# PG05_Power_Conversions.net
KiCad netlist of a schematic drawn in Altium Designer
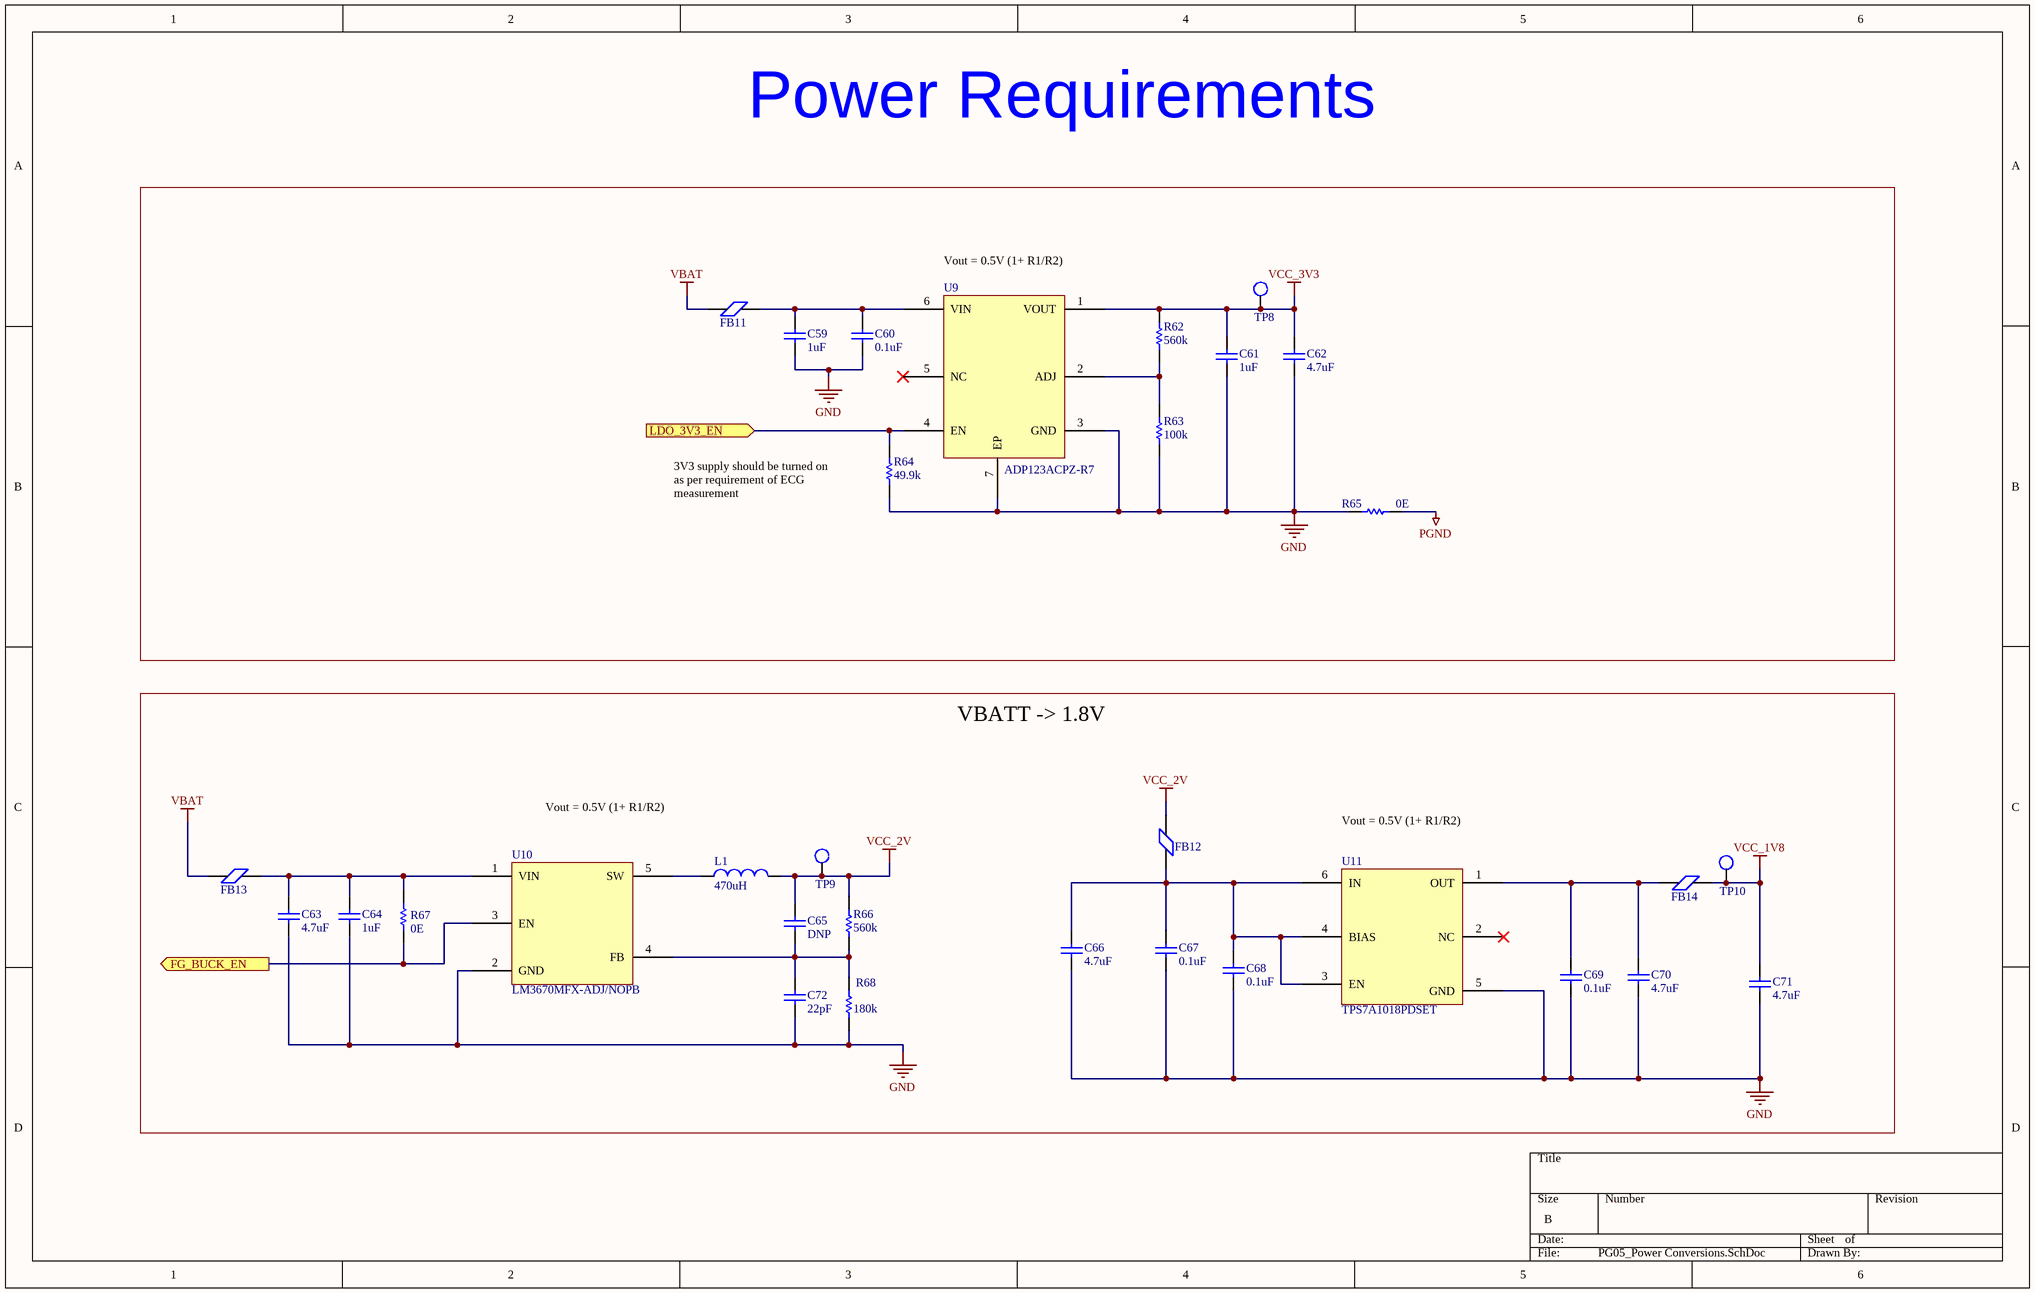
[diagram p0: PG05_Power Conversions.SchDoc]

(export (version "E")
  (design (tool "Eeschema 10.0.6"))
  (components
    (comp (ref "C59")
      (value "1uF")
      (footprint "0805C")
      (description "CAP CER 1UF 25V X7R 0805")
      (libsource (lib "Smart Ring Components") (part "CAP_0805_1uF_25V"))
    )
    (comp (ref "C60")
      (value "0.1uF")
      (footprint "0402C")
      (description "CAP CER 0.1UF 50V X7R 0402")
      (libsource (lib "Smart Ring Components") (part "CAP_0402_0.1uF_50V"))
    )
    (comp (ref "C61")
      (value "1uF")
      (footprint "0805C")
      (description "CAP CER 1UF 25V X7R 0805")
      (libsource (lib "Smart Ring Components") (part "CAP_0805_1uF_25V"))
    )
    (comp (ref "C62")
      (value "4.7uF")
      (footprint "0805C")
      (description "CAP CER MLCC 4.7uF X7R 16V  0805")
      (libsource (lib "Smart Ring Components") (part "CAP_0805_4.7uF_16V"))
    )
    (comp (ref "C63")
      (value "4.7uF")
      (footprint "0805C")
      (description "CAP CER MLCC 4.7uF X7R 16V  0805")
      (libsource (lib "Smart Ring Components") (part "CAP_0805_4.7uF_16V"))
    )
    (comp (ref "C64")
      (value "1uF")
      (footprint "0805C")
      (description "CAP CER 1UF 25V X7R 0805")
      (libsource (lib "Smart Ring Components") (part "CAP_0805_1uF_25V"))
    )
    (comp (ref "C65")
      (value "DNP")
      (footprint "0402C")
      (description "CAP CER DNP 0402")
      (fields (field (name "MFR") "Generic"))
      (libsource (lib "Smart Ring Components") (part "CAP_0402_DNP"))
    )
    (comp (ref "C66")
      (value "4.7uF")
      (footprint "0805C")
      (description "CAP CER MLCC 4.7uF X7R 16V  0805")
      (libsource (lib "Smart Ring Components") (part "CAP_0805_4.7uF_16V"))
    )
    (comp (ref "C67")
      (value "0.1uF")
      (footprint "0402C")
      (description "CAP CER 0.1UF 50V X7R 0402")
      (libsource (lib "Smart Ring Components") (part "CAP_0402_0.1uF_50V"))
    )
    (comp (ref "C68")
      (value "0.1uF")
      (footprint "0402C")
      (description "CAP CER 0.1UF 50V X7R 0402")
      (libsource (lib "Smart Ring Components") (part "CAP_0402_0.1uF_50V"))
    )
    (comp (ref "C69")
      (value "0.1uF")
      (footprint "0402C")
      (description "CAP CER 0.1UF 50V X7R 0402")
      (libsource (lib "Smart Ring Components") (part "CAP_0402_0.1uF_50V"))
    )
    (comp (ref "C70")
      (value "4.7uF")
      (footprint "0805C")
      (description "CAP CER MLCC 4.7uF X7R 16V  0805")
      (libsource (lib "Smart Ring Components") (part "CAP_0805_4.7uF_16V"))
    )
    (comp (ref "C71")
      (value "4.7uF")
      (footprint "0805C")
      (description "CAP CER MLCC 4.7uF X7R 16V  0805")
      (libsource (lib "Smart Ring Components") (part "CAP_0805_4.7uF_16V"))
    )
    (comp (ref "C72")
      (value "22pF")
      (footprint "0402C")
      (description "CAP CER 22PF 50V C0G 0402")
      (fields (field (name "MFR") "Generic"))
      (libsource (lib "Smart Ring Components") (part "CAP_0402_22pF"))
    )
    (comp (ref "FB11")
      (value "Ferrite Bead")
      (footprint "0402R")
      (description "CHIP BEAD 600 OHM 0402 300mA")
      (fields (field (name "MFR") "Walsin") (field (name "MPN") "WLBD1005K2U601TP"))
      (libsource (lib "Smart Ring Components") (part "Ferrite Bead"))
    )
    (comp (ref "FB12")
      (value "Ferrite Bead")
      (footprint "0402R")
      (description "CHIP BEAD 600 OHM 0402 300mA")
      (fields (field (name "MFR") "Walsin") (field (name "MPN") "WLBD1005K2U601TP"))
      (libsource (lib "Smart Ring Components") (part "Ferrite Bead"))
    )
    (comp (ref "FB13")
      (value "Ferrite Bead")
      (footprint "0402R")
      (description "CHIP BEAD 600 OHM 0402 300mA")
      (fields (field (name "MFR") "Walsin") (field (name "MPN") "WLBD1005K2U601TP"))
      (libsource (lib "Smart Ring Components") (part "Ferrite Bead"))
    )
    (comp (ref "FB14")
      (value "Ferrite Bead")
      (footprint "0402R")
      (description "CHIP BEAD 600 OHM 0402 300mA")
      (fields (field (name "MFR") "Walsin") (field (name "MPN") "WLBD1005K2U601TP"))
      (libsource (lib "Smart Ring Components") (part "Ferrite Bead"))
    )
    (comp (ref "L1")
      (value "470uH")
      (footprint "NR6028T3R0N")
      (description "FIXED IND 470UH 105MA 14.3OHM SM")
      (fields (field (name "MFR") "Bourns") (field (name "MPN") "SDR0302-471KL"))
      (libsource (lib "Smart Ring Components") (part "IND_470uH"))
    )
    (comp (ref "R62")
      (value "560k")
      (footprint "0402R")
      (description "RES 560K OHM 1% 1/16W 0402")
      (fields (field (name "MFR") "Generic"))
      (libsource (lib "Smart Ring Components") (part "RES_0402_560k"))
    )
    (comp (ref "R63")
      (value "100k")
      (footprint "0402R")
      (description "RES 100K OHM 1% 1/16W 0402")
      (fields (field (name "MFR") "Generic"))
      (libsource (lib "Smart Ring Components") (part "RES_0402_100k"))
    )
    (comp (ref "R64")
      (value "49.9k")
      (footprint "0402R")
      (description "RES 49.9K OHM 1% 1/16W 0402")
      (fields (field (name "MFR") "Generic"))
      (libsource (lib "Smart Ring Components") (part "RES_0402_49.9k"))
    )
    (comp (ref "R65")
      (value "0E")
      (footprint "0402R")
      (description "RES 0 OHM JUMPER 1/16W 0402")
      (fields (field (name "MFR") "Generic"))
      (libsource (lib "Smart Ring Components") (part "RES_0402_0E"))
    )
    (comp (ref "R66")
      (value "560k")
      (footprint "0402R")
      (description "RES 560K OHM 1% 1/16W 0402")
      (fields (field (name "MFR") "Generic"))
      (libsource (lib "Smart Ring Components") (part "RES_0402_560k"))
    )
    (comp (ref "R67")
      (value "0E")
      (footprint "0402R")
      (description "RES 0 OHM JUMPER 1/16W 0402")
      (fields (field (name "MFR") "Generic"))
      (libsource (lib "Smart Ring Components") (part "RES_0402_0E"))
    )
    (comp (ref "R68")
      (value "180k")
      (footprint "0402R")
      (description "RES 180K OHM 1% 1/16W 0402")
      (fields (field (name "MFR") "Generic"))
      (libsource (lib "Smart Ring Components") (part "RES_0402_180k"))
    )
    (comp (ref "TP8")
      (value "Test_Point")
      (footprint "TP")
      (libsource (lib "Smart Ring Components") (part "Test_Point"))
    )
    (comp (ref "TP9")
      (value "Test_Point")
      (footprint "TP")
      (libsource (lib "Smart Ring Components") (part "Test_Point"))
    )
    (comp (ref "TP10")
      (value "Test_Point")
      (footprint "TP")
      (libsource (lib "Smart Ring Components") (part "Test_Point"))
    )
    (comp (ref "U9")
      (value "ADP123ACPZ-R7")
      (footprint "ADP123ACPZ-R7")
      (description "IC REG LIN POS ADJ 300MA 6LFCSP")
      (fields (field (name "MFR") "Analog Devices"))
      (libsource (lib "Smart Ring Components") (part "LDO_ADP123ACPZ-R7"))
    )
    (comp (ref "U10")
      (value "LM3670MFX-ADJ/NOPB")
      (footprint "LM3670MFX-ADJ/NOPB")
      (description "IC REG BUCK ADJ 350MA SOT23-5")
      (fields (field (name "MFR") "Texas Instruments"))
      (libsource (lib "Smart Ring Components") (part "Buck_LM3670MFX-ADJ/NOPB"))
    )
    (comp (ref "U11")
      (value "TPS7A1018PDSET")
      (footprint "TPS7A1018PDSET")
      (description "IC REG LINEAR 1.8V 300MA 6WSON")
      (fields (field (name "MFR") "TI"))
      (libsource (lib "Smart Ring Components") (part "LDO_TPS7A1018PDSET"))
    )
  )
  (nets
    (net (code "1") (name "/FG_BUCK_EN") (class "Default")
      (node (ref "R67") (pin "1") (pinfunction "1_1") (pintype "passive"))
      (node (ref "U10") (pin "3") (pinfunction "EN_3") (pintype "passive"))
    )
    (net (code "2") (name "/LDO_3V3_EN") (class "Default")
      (node (ref "R64") (pin "2") (pinfunction "2_2") (pintype "passive"))
      (node (ref "U9") (pin "4") (pinfunction "EN_4") (pintype "power_in"))
    )
    (net (code "3") (name "GND") (class "Default")
      (node (ref "C59") (pin "1") (pinfunction "1_1") (pintype "passive"))
      (node (ref "C60") (pin "1") (pinfunction "1_1") (pintype "passive"))
      (node (ref "C61") (pin "1") (pinfunction "1_1") (pintype "passive"))
      (node (ref "C62") (pin "1") (pinfunction "1_1") (pintype "passive"))
      (node (ref "C63") (pin "1") (pinfunction "1_1") (pintype "passive"))
      (node (ref "C64") (pin "1") (pinfunction "1_1") (pintype "passive"))
      (node (ref "C66") (pin "1") (pinfunction "1_1") (pintype "passive"))
      (node (ref "C67") (pin "1") (pinfunction "1_1") (pintype "passive"))
      (node (ref "C68") (pin "1") (pinfunction "1_1") (pintype "passive"))
      (node (ref "C69") (pin "1") (pinfunction "1_1") (pintype "passive"))
      (node (ref "C70") (pin "1") (pinfunction "1_1") (pintype "passive"))
      (node (ref "C71") (pin "1") (pinfunction "1_1") (pintype "passive"))
      (node (ref "C72") (pin "1") (pinfunction "1_1") (pintype "passive"))
      (node (ref "R63") (pin "1") (pinfunction "1_1") (pintype "passive"))
      (node (ref "R64") (pin "1") (pinfunction "1_1") (pintype "passive"))
      (node (ref "R65") (pin "1") (pinfunction "1_1") (pintype "passive"))
      (node (ref "R68") (pin "1") (pinfunction "1_1") (pintype "passive"))
      (node (ref "U10") (pin "2") (pinfunction "GND_2") (pintype "power_in"))
      (node (ref "U11") (pin "5") (pinfunction "GND_5") (pintype "power_in"))
      (node (ref "U9") (pin "3") (pinfunction "GND_3") (pintype "power_in"))
      (node (ref "U9") (pin "7") (pinfunction "EP_7") (pintype "power_in"))
    )
    (net (code "4") (name "Net-(U9-ADJ)") (class "Default")
      (node (ref "R62") (pin "1") (pinfunction "1_1") (pintype "passive"))
      (node (ref "R63") (pin "2") (pinfunction "2_2") (pintype "passive"))
      (node (ref "U9") (pin "2") (pinfunction "ADJ_2") (pintype "power_in"))
    )
    (net (code "5") (name "Net-(U9-VIN)") (class "Default")
      (node (ref "C59") (pin "2") (pinfunction "2_2") (pintype "passive"))
      (node (ref "C60") (pin "2") (pinfunction "2_2") (pintype "passive"))
      (node (ref "FB11") (pin "2") (pinfunction "VREF_2") (pintype "passive"))
      (node (ref "U9") (pin "6") (pinfunction "VIN_6") (pintype "power_in"))
    )
    (net (code "6") (name "Net-(U10-FB)") (class "Default")
      (node (ref "C65") (pin "2") (pinfunction "2_2") (pintype "passive"))
      (node (ref "C72") (pin "2") (pinfunction "2_2") (pintype "passive"))
      (node (ref "R66") (pin "1") (pinfunction "1_1") (pintype "passive"))
      (node (ref "R68") (pin "2") (pinfunction "2_2") (pintype "passive"))
      (node (ref "U10") (pin "4") (pinfunction "FB_4") (pintype "power_in"))
    )
    (net (code "7") (name "Net-(U10-SW)") (class "Default")
      (node (ref "L1") (pin "1") (pinfunction "1_1") (pintype "passive"))
      (node (ref "U10") (pin "5") (pinfunction "SW_5") (pintype "passive"))
    )
    (net (code "8") (name "Net-(U10-VIN)") (class "Default")
      (node (ref "C63") (pin "2") (pinfunction "2_2") (pintype "passive"))
      (node (ref "C64") (pin "2") (pinfunction "2_2") (pintype "passive"))
      (node (ref "FB13") (pin "2") (pinfunction "VREF_2") (pintype "passive"))
      (node (ref "R67") (pin "2") (pinfunction "2_2") (pintype "passive"))
      (node (ref "U10") (pin "1") (pinfunction "VIN_1") (pintype "power_in"))
    )
    (net (code "9") (name "Net-(U11-BIAS)") (class "Default")
      (node (ref "C66") (pin "2") (pinfunction "2_2") (pintype "passive"))
      (node (ref "C67") (pin "2") (pinfunction "2_2") (pintype "passive"))
      (node (ref "C68") (pin "2") (pinfunction "2_2") (pintype "passive"))
      (node (ref "FB12") (pin "1") (pinfunction "VREF_1") (pintype "passive"))
      (node (ref "U11") (pin "3") (pinfunction "EN_3") (pintype "passive"))
      (node (ref "U11") (pin "4") (pinfunction "BIAS_4") (pintype "passive"))
      (node (ref "U11") (pin "6") (pinfunction "IN_6") (pintype "power_in"))
    )
    (net (code "10") (name "Net-(U11-OUT)") (class "Default")
      (node (ref "C69") (pin "2") (pinfunction "2_2") (pintype "passive"))
      (node (ref "C70") (pin "2") (pinfunction "2_2") (pintype "passive"))
      (node (ref "FB14") (pin "1") (pinfunction "VREF_1") (pintype "passive"))
      (node (ref "U11") (pin "1") (pinfunction "OUT_1") (pintype "power_in"))
    )
    (net (code "11") (name "PGND") (class "Default")
      (node (ref "R65") (pin "2") (pinfunction "2_2") (pintype "passive"))
    )
    (net (code "12") (name "VBAT") (class "Default")
      (node (ref "FB11") (pin "1") (pinfunction "VREF_1") (pintype "passive"))
      (node (ref "FB13") (pin "1") (pinfunction "VREF_1") (pintype "passive"))
    )
    (net (code "13") (name "VCC_1V8") (class "Default")
      (node (ref "C71") (pin "2") (pinfunction "2_2") (pintype "passive"))
      (node (ref "FB14") (pin "2") (pinfunction "VREF_2") (pintype "passive"))
      (node (ref "TP10") (pin "1") (pintype "passive"))
    )
    (net (code "14") (name "VCC_2V") (class "Default")
      (node (ref "C65") (pin "1") (pinfunction "1_1") (pintype "passive"))
      (node (ref "FB12") (pin "2") (pinfunction "VREF_2") (pintype "passive"))
      (node (ref "L1") (pin "2") (pinfunction "2_2") (pintype "passive"))
      (node (ref "R66") (pin "2") (pinfunction "2_2") (pintype "passive"))
      (node (ref "TP9") (pin "1") (pintype "passive"))
    )
    (net (code "15") (name "VCC_3V3") (class "Default")
      (node (ref "C61") (pin "2") (pinfunction "2_2") (pintype "passive"))
      (node (ref "C62") (pin "2") (pinfunction "2_2") (pintype "passive"))
      (node (ref "R62") (pin "2") (pinfunction "2_2") (pintype "passive"))
      (node (ref "TP8") (pin "1") (pintype "passive"))
      (node (ref "U9") (pin "1") (pinfunction "VOUT_1") (pintype "passive"))
    )
    (net (code "16") (name "unconnected-(U9-NC-Pad5)") (class "Default")
      (node (ref "U9") (pin "5") (pinfunction "NC_5") (pintype "passive+no_connect"))
    )
    (net (code "17") (name "unconnected-(U11-NC-Pad2)") (class "Default")
      (node (ref "U11") (pin "2") (pinfunction "NC_2") (pintype "passive+no_connect"))
    )
  )
)
